# IHM_ADAPT.net
KiCad netlist of a schematic drawn in EAGLE
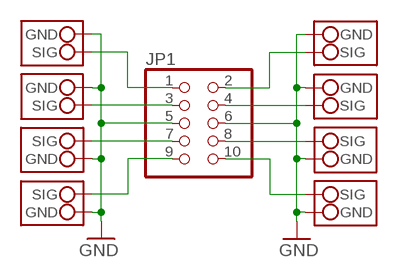
[diagram p0: schematic, sheet 1]

(export (version "E")
  (design (tool "Eeschema 10.0.6"))
  (components
    (comp (ref "JP1")
      (value "PINHD-2X05_2.54-SMD")
      (footprint "eagle-import:2X05SMD")
      (libsource (lib "eagle-import") (part "PINHD-2X05_2.54-SMD"))
    )
    (comp (ref "U$1")
      (value "CONN_WIRE")
      (footprint "eagle-import:SMD_WIRE_CON")
      (libsource (lib "eagle-import") (part "CONN_WIRE"))
    )
    (comp (ref "U$2")
      (value "CONN_WIRE")
      (footprint "eagle-import:SMD_WIRE_CON")
      (libsource (lib "eagle-import") (part "CONN_WIRE"))
    )
    (comp (ref "U$3")
      (value "CONN_WIRE")
      (footprint "eagle-import:SMD_WIRE_CON")
      (libsource (lib "eagle-import") (part "CONN_WIRE"))
    )
    (comp (ref "U$4")
      (value "CONN_WIRE")
      (footprint "eagle-import:SMD_WIRE_CON")
      (libsource (lib "eagle-import") (part "CONN_WIRE"))
    )
    (comp (ref "U$5")
      (value "CONN_WIRE")
      (footprint "eagle-import:SMD_WIRE_CON")
      (libsource (lib "eagle-import") (part "CONN_WIRE"))
    )
    (comp (ref "U$6")
      (value "CONN_WIRE")
      (footprint "eagle-import:SMD_WIRE_CON")
      (libsource (lib "eagle-import") (part "CONN_WIRE"))
    )
    (comp (ref "U$7")
      (value "CONN_WIRE")
      (footprint "eagle-import:SMD_WIRE_CON")
      (libsource (lib "eagle-import") (part "CONN_WIRE"))
    )
    (comp (ref "U$8")
      (value "CONN_WIRE")
      (footprint "eagle-import:SMD_WIRE_CON")
      (libsource (lib "eagle-import") (part "CONN_WIRE"))
    )
  )
  (nets
    (net (code "1") (name "GND") (class "Default")
      (node (ref "JP1") (pin "5") (pinfunction "5_5") (pintype "passive"))
      (node (ref "JP1") (pin "6") (pinfunction "6_6") (pintype "passive"))
      (node (ref "U$1") (pin "P$1") (pinfunction "GND_P$1") (pintype "bidirectional"))
      (node (ref "U$2") (pin "P$1") (pinfunction "GND_P$1") (pintype "bidirectional"))
      (node (ref "U$3") (pin "P$1") (pinfunction "GND_P$1") (pintype "bidirectional"))
      (node (ref "U$4") (pin "P$1") (pinfunction "GND_P$1") (pintype "bidirectional"))
      (node (ref "U$5") (pin "P$1") (pinfunction "GND_P$1") (pintype "bidirectional"))
      (node (ref "U$6") (pin "P$1") (pinfunction "GND_P$1") (pintype "bidirectional"))
      (node (ref "U$7") (pin "P$1") (pinfunction "GND_P$1") (pintype "bidirectional"))
      (node (ref "U$8") (pin "P$1") (pinfunction "GND_P$1") (pintype "bidirectional"))
    )
    (net (code "2") (name "Net-(U$1-SIG)") (class "Default")
      (node (ref "JP1") (pin "4") (pinfunction "4_4") (pintype "passive"))
      (node (ref "U$1") (pin "P$2") (pinfunction "SIG_P$2") (pintype "bidirectional"))
    )
    (net (code "3") (name "Net-(U$2-SIG)") (class "Default")
      (node (ref "JP1") (pin "8") (pinfunction "8_8") (pintype "passive"))
      (node (ref "U$2") (pin "P$2") (pinfunction "SIG_P$2") (pintype "bidirectional"))
    )
    (net (code "4") (name "Net-(U$3-SIG)") (class "Default")
      (node (ref "JP1") (pin "2") (pinfunction "2_2") (pintype "passive"))
      (node (ref "U$3") (pin "P$2") (pinfunction "SIG_P$2") (pintype "bidirectional"))
    )
    (net (code "5") (name "Net-(U$4-SIG)") (class "Default")
      (node (ref "JP1") (pin "10") (pinfunction "10_10") (pintype "passive"))
      (node (ref "U$4") (pin "P$2") (pinfunction "SIG_P$2") (pintype "bidirectional"))
    )
    (net (code "6") (name "Net-(U$5-SIG)") (class "Default")
      (node (ref "JP1") (pin "3") (pinfunction "3_3") (pintype "passive"))
      (node (ref "U$5") (pin "P$2") (pinfunction "SIG_P$2") (pintype "bidirectional"))
    )
    (net (code "7") (name "Net-(U$6-SIG)") (class "Default")
      (node (ref "JP1") (pin "7") (pinfunction "7_7") (pintype "passive"))
      (node (ref "U$6") (pin "P$2") (pinfunction "SIG_P$2") (pintype "bidirectional"))
    )
    (net (code "8") (name "Net-(U$7-SIG)") (class "Default")
      (node (ref "JP1") (pin "1") (pinfunction "1_1") (pintype "passive"))
      (node (ref "U$7") (pin "P$2") (pinfunction "SIG_P$2") (pintype "bidirectional"))
    )
    (net (code "9") (name "Net-(U$8-SIG)") (class "Default")
      (node (ref "JP1") (pin "9") (pinfunction "9_9") (pintype "passive"))
      (node (ref "U$8") (pin "P$2") (pinfunction "SIG_P$2") (pintype "bidirectional"))
    )
  )
)
